# dRGBblades.net
KiCad netlist of a schematic drawn in EAGLE
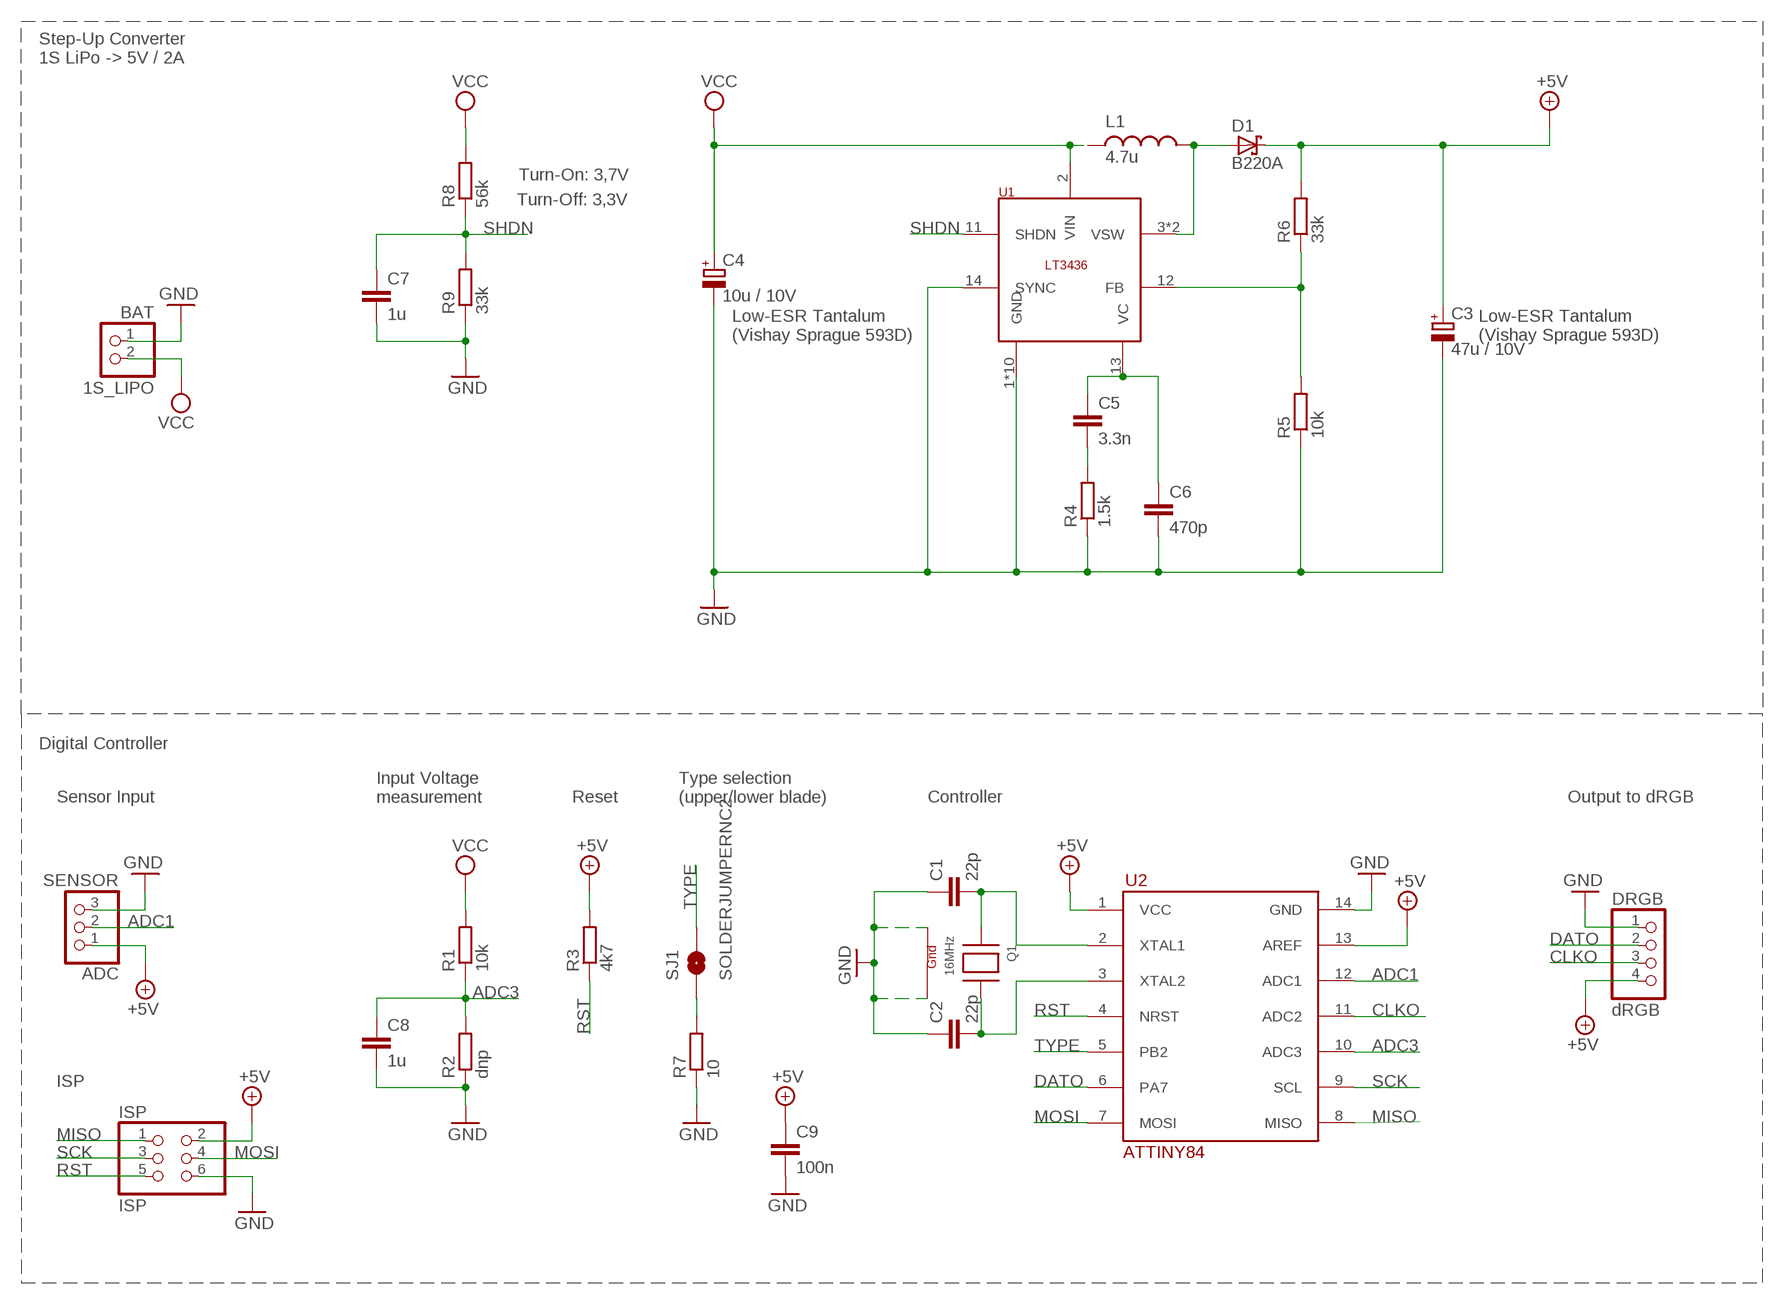
[diagram p0: schematic, sheet 1]

(export (version "E")
  (design (tool "Eeschema 10.0.6"))
  (components
    (comp (ref "ADC")
      (value "SENSOR")
      (footprint "eagle-import:1X03_90")
      (libsource (lib "eagle-import") (part "PINHD-1X3/90"))
    )
    (comp (ref "BAT")
      (value "1S_LIPO")
      (footprint "eagle-import:1X02_90")
      (libsource (lib "eagle-import") (part "PINHD-1X2/90"))
    )
    (comp (ref "C1")
      (value "22p")
      (footprint "eagle-import:C0603")
      (libsource (lib "eagle-import") (part "C-EUC0603"))
    )
    (comp (ref "C2")
      (value "22p")
      (footprint "eagle-import:C0603")
      (libsource (lib "eagle-import") (part "C-EUC0603"))
    )
    (comp (ref "C3")
      (value "47u / 10V")
      (footprint "eagle-import:D_7343-31W")
      (libsource (lib "eagle-import") (part "CPOL-EUD/7343-31W"))
    )
    (comp (ref "C4")
      (value "10u / 10V")
      (footprint "eagle-import:A_3216-18W")
      (libsource (lib "eagle-import") (part "CPOL-EUA/3216-18W"))
    )
    (comp (ref "C5")
      (value "3.3n")
      (footprint "eagle-import:C0603")
      (libsource (lib "eagle-import") (part "C-EUC0603"))
    )
    (comp (ref "C6")
      (value "470p")
      (footprint "eagle-import:C0603")
      (libsource (lib "eagle-import") (part "C-EUC0603"))
    )
    (comp (ref "C7")
      (value "1u")
      (footprint "eagle-import:C0603")
      (libsource (lib "eagle-import") (part "C-EUC0603"))
    )
    (comp (ref "C8")
      (value "1u")
      (footprint "eagle-import:C0603")
      (libsource (lib "eagle-import") (part "C-EUC0603"))
    )
    (comp (ref "C9")
      (value "100n")
      (footprint "eagle-import:C0603")
      (libsource (lib "eagle-import") (part "C-EUC0603"))
    )
    (comp (ref "D1")
      (value "B220A")
      (footprint "eagle-import:SMA")
      (libsource (lib "eagle-import") (part "B220A"))
    )
    (comp (ref "DRGB")
      (value "dRGB")
      (footprint "eagle-import:1X04_90")
      (libsource (lib "eagle-import") (part "PINHD-1X4/90"))
    )
    (comp (ref "ISP")
      (value "ISP")
      (footprint "eagle-import:2X03_90")
      (libsource (lib "eagle-import") (part "PINHD-2X3/90"))
    )
    (comp (ref "L1")
      (value "4.7u")
      (footprint "eagle-import:INDUCTOR-SUMIDA-CDRH6")
      (libsource (lib "eagle-import") (part "INDUCTOR-SUMIDA-CDRH6"))
    )
    (comp (ref "Q1")
      (value "16MHz")
      (footprint "eagle-import:NX3225")
      (libsource (lib "eagle-import") (part "XTAL-4-3225"))
    )
    (comp (ref "R1")
      (value "10k")
      (footprint "eagle-import:R0603")
      (libsource (lib "eagle-import") (part "R-EUR0603"))
    )
    (comp (ref "R2")
      (value "dnp")
      (footprint "eagle-import:R0603")
      (libsource (lib "eagle-import") (part "R-EUR0603"))
    )
    (comp (ref "R3")
      (value "4k7")
      (footprint "eagle-import:R0603")
      (libsource (lib "eagle-import") (part "R-EUR0603"))
    )
    (comp (ref "R4")
      (value "1.5k")
      (footprint "eagle-import:R0603")
      (libsource (lib "eagle-import") (part "R-EUR0603"))
    )
    (comp (ref "R5")
      (value "10k")
      (footprint "eagle-import:R0603")
      (libsource (lib "eagle-import") (part "R-EUR0603"))
    )
    (comp (ref "R6")
      (value "33k")
      (footprint "eagle-import:R0603")
      (libsource (lib "eagle-import") (part "R-EUR0603"))
    )
    (comp (ref "R7")
      (value "10")
      (footprint "eagle-import:R0603")
      (libsource (lib "eagle-import") (part "R-EUR0603"))
    )
    (comp (ref "R8")
      (value "56k")
      (footprint "eagle-import:R0603")
      (libsource (lib "eagle-import") (part "R-EUR0603"))
    )
    (comp (ref "R9")
      (value "33k")
      (footprint "eagle-import:R0603")
      (libsource (lib "eagle-import") (part "R-EUR0603"))
    )
    (comp (ref "SJ1")
      (value "SOLDERJUMPERNC2")
      (footprint "eagle-import:SJ_2S-NOTRACE")
      (libsource (lib "eagle-import") (part "SOLDERJUMPERNC2"))
    )
    (comp (ref "U1")
      (value "LT3436")
      (footprint "eagle-import:TSSOP-17")
      (libsource (lib "eagle-import") (part "LT3436"))
    )
    (comp (ref "U2")
      (value "ATTINY84")
      (footprint "eagle-import:SO14")
      (libsource (lib "eagle-import") (part "ATTINY84"))
    )
  )
  (nets
    (net (code "1") (name "+5V") (class "Default")
      (node (ref "ADC") (pin "1") (pinfunction "1_1") (pintype "passive"))
      (node (ref "C3") (pin "+") (pinfunction "+_+") (pintype "passive"))
      (node (ref "C9") (pin "1") (pinfunction "1_1") (pintype "passive"))
      (node (ref "D1") (pin "C") (pinfunction "C_C") (pintype "passive"))
      (node (ref "DRGB") (pin "4") (pinfunction "4_4") (pintype "passive"))
      (node (ref "ISP") (pin "2") (pinfunction "2_2") (pintype "passive"))
      (node (ref "R3") (pin "2") (pinfunction "2_2") (pintype "passive"))
      (node (ref "R6") (pin "2") (pinfunction "2_2") (pintype "passive"))
      (node (ref "U2") (pin "1") (pinfunction "VCC_1") (pintype "input"))
      (node (ref "U2") (pin "13") (pinfunction "AREF_13") (pintype "input"))
    )
    (net (code "2") (name "/ADC1") (class "Default")
      (node (ref "ADC") (pin "2") (pinfunction "2_2") (pintype "passive"))
      (node (ref "U2") (pin "12") (pinfunction "ADC1_12") (pintype "input"))
    )
    (net (code "3") (name "/ADC3") (class "Default")
      (node (ref "C8") (pin "1") (pinfunction "1_1") (pintype "passive"))
      (node (ref "R1") (pin "1") (pinfunction "1_1") (pintype "passive"))
      (node (ref "R2") (pin "2") (pinfunction "2_2") (pintype "passive"))
      (node (ref "U2") (pin "10") (pinfunction "ADC3_10") (pintype "input"))
    )
    (net (code "4") (name "/CLKO") (class "Default")
      (node (ref "DRGB") (pin "3") (pinfunction "3_3") (pintype "passive"))
      (node (ref "U2") (pin "11") (pinfunction "ADC2_11") (pintype "passive"))
    )
    (net (code "5") (name "/DATO") (class "Default")
      (node (ref "DRGB") (pin "2") (pinfunction "2_2") (pintype "passive"))
      (node (ref "U2") (pin "6") (pinfunction "PA7_6") (pintype "bidirectional"))
    )
    (net (code "6") (name "/MISO") (class "Default")
      (node (ref "ISP") (pin "1") (pinfunction "1_1") (pintype "passive"))
      (node (ref "U2") (pin "8") (pinfunction "MISO_8") (pintype "input"))
    )
    (net (code "7") (name "/MOSI") (class "Default")
      (node (ref "ISP") (pin "4") (pinfunction "4_4") (pintype "passive"))
      (node (ref "U2") (pin "7") (pinfunction "MOSI_7") (pintype "output"))
    )
    (net (code "8") (name "/RST") (class "Default")
      (node (ref "ISP") (pin "5") (pinfunction "5_5") (pintype "passive"))
      (node (ref "R3") (pin "1") (pinfunction "1_1") (pintype "passive"))
      (node (ref "U2") (pin "4") (pinfunction "NRST_4") (pintype "input"))
    )
    (net (code "9") (name "/SCK") (class "Default")
      (node (ref "ISP") (pin "3") (pinfunction "3_3") (pintype "passive"))
      (node (ref "U2") (pin "9") (pinfunction "SCL_9") (pintype "output"))
    )
    (net (code "10") (name "/SHDN") (class "Default")
      (node (ref "C7") (pin "1") (pinfunction "1_1") (pintype "passive"))
      (node (ref "R8") (pin "1") (pinfunction "1_1") (pintype "passive"))
      (node (ref "R9") (pin "2") (pinfunction "2_2") (pintype "passive"))
      (node (ref "U1") (pin "11") (pinfunction "SHDN_11") (pintype "input"))
    )
    (net (code "11") (name "/TYPE") (class "Default")
      (node (ref "SJ1") (pin "2") (pinfunction "2_2") (pintype "passive"))
      (node (ref "U2") (pin "5") (pinfunction "PB2_5") (pintype "bidirectional"))
    )
    (net (code "12") (name "GND") (class "Default")
      (node (ref "ADC") (pin "3") (pinfunction "3_3") (pintype "passive"))
      (node (ref "BAT") (pin "1") (pinfunction "1_1") (pintype "passive"))
      (node (ref "C1") (pin "1") (pinfunction "1_1") (pintype "passive"))
      (node (ref "C2") (pin "1") (pinfunction "1_1") (pintype "passive"))
      (node (ref "C3") (pin "-") (pinfunction "-_-") (pintype "passive"))
      (node (ref "C4") (pin "-") (pinfunction "-_-") (pintype "passive"))
      (node (ref "C6") (pin "2") (pinfunction "2_2") (pintype "passive"))
      (node (ref "C7") (pin "2") (pinfunction "2_2") (pintype "passive"))
      (node (ref "C8") (pin "2") (pinfunction "2_2") (pintype "passive"))
      (node (ref "C9") (pin "2") (pinfunction "2_2") (pintype "passive"))
      (node (ref "DRGB") (pin "1") (pinfunction "1_1") (pintype "passive"))
      (node (ref "ISP") (pin "6") (pinfunction "6_6") (pintype "passive"))
      (node (ref "Q1") (pin "2") (pinfunction "G2_2") (pintype "power_in"))
      (node (ref "Q1") (pin "4") (pinfunction "G1_4") (pintype "power_in"))
      (node (ref "R2") (pin "1") (pinfunction "1_1") (pintype "passive"))
      (node (ref "R4") (pin "1") (pinfunction "1_1") (pintype "passive"))
      (node (ref "R5") (pin "1") (pinfunction "1_1") (pintype "passive"))
      (node (ref "R7") (pin "1") (pinfunction "1_1") (pintype "passive"))
      (node (ref "R9") (pin "1") (pinfunction "1_1") (pintype "passive"))
      (node (ref "U1") (pin "1") (pinfunction "GND_1") (pintype "power_in"))
      (node (ref "U1") (pin "10") (pinfunction "GND_10") (pintype "power_in"))
      (node (ref "U1") (pin "14") (pinfunction "SYNC_14") (pintype "input"))
      (node (ref "U1") (pin "15") (pinfunction "GND_15") (pintype "power_in"))
      (node (ref "U1") (pin "16") (pinfunction "GND_16") (pintype "power_in"))
      (node (ref "U1") (pin "17") (pinfunction "GND_17") (pintype "power_in"))
      (node (ref "U1") (pin "5") (pinfunction "GND_5") (pintype "power_in"))
      (node (ref "U1") (pin "6") (pinfunction "GND_6") (pintype "power_in"))
      (node (ref "U1") (pin "7") (pinfunction "GND_7") (pintype "power_in"))
      (node (ref "U1") (pin "8") (pinfunction "GND_8") (pintype "power_in"))
      (node (ref "U1") (pin "9") (pinfunction "GND_9") (pintype "power_in"))
      (node (ref "U2") (pin "14") (pinfunction "GND_14") (pintype "power_in"))
    )
    (net (code "13") (name "Net-(C5-Pad2)") (class "Default")
      (node (ref "C5") (pin "2") (pinfunction "2_2") (pintype "passive"))
      (node (ref "R4") (pin "2") (pinfunction "2_2") (pintype "passive"))
    )
    (net (code "14") (name "Net-(D1-PadA)") (class "Default")
      (node (ref "D1") (pin "A") (pinfunction "A_A") (pintype "passive"))
      (node (ref "L1") (pin "P$2") (pinfunction "P$2_P$2") (pintype "bidirectional"))
      (node (ref "U1") (pin "3") (pinfunction "VSW_3") (pintype "output"))
      (node (ref "U1") (pin "4") (pinfunction "VSW_4") (pintype "output"))
    )
    (net (code "15") (name "Net-(Q1-X1)") (class "Default")
      (node (ref "C1") (pin "2") (pinfunction "2_2") (pintype "passive"))
      (node (ref "Q1") (pin "1") (pinfunction "X1_1") (pintype "bidirectional"))
      (node (ref "U2") (pin "2") (pinfunction "XTAL1_2") (pintype "bidirectional"))
    )
    (net (code "16") (name "Net-(Q1-X2)") (class "Default")
      (node (ref "C2") (pin "2") (pinfunction "2_2") (pintype "passive"))
      (node (ref "Q1") (pin "3") (pinfunction "X2_3") (pintype "bidirectional"))
      (node (ref "U2") (pin "3") (pinfunction "XTAL2_3") (pintype "bidirectional"))
    )
    (net (code "17") (name "Net-(R7-Pad2)") (class "Default")
      (node (ref "R7") (pin "2") (pinfunction "2_2") (pintype "passive"))
      (node (ref "SJ1") (pin "1") (pinfunction "1_1") (pintype "passive"))
    )
    (net (code "18") (name "Net-(U1-FB)") (class "Default")
      (node (ref "R5") (pin "2") (pinfunction "2_2") (pintype "passive"))
      (node (ref "R6") (pin "1") (pinfunction "1_1") (pintype "passive"))
      (node (ref "U1") (pin "12") (pinfunction "FB_12") (pintype "input"))
    )
    (net (code "19") (name "Net-(U1-VC)") (class "Default")
      (node (ref "C5") (pin "1") (pinfunction "1_1") (pintype "passive"))
      (node (ref "C6") (pin "1") (pinfunction "1_1") (pintype "passive"))
      (node (ref "U1") (pin "13") (pinfunction "VC_13") (pintype "output"))
    )
    (net (code "20") (name "VCC") (class "Default")
      (node (ref "BAT") (pin "2") (pinfunction "2_2") (pintype "passive"))
      (node (ref "C4") (pin "+") (pinfunction "+_+") (pintype "passive"))
      (node (ref "L1") (pin "P$1") (pinfunction "P$1_P$1") (pintype "bidirectional"))
      (node (ref "R1") (pin "2") (pinfunction "2_2") (pintype "passive"))
      (node (ref "R8") (pin "2") (pinfunction "2_2") (pintype "passive"))
      (node (ref "U1") (pin "2") (pinfunction "VIN_2") (pintype "input"))
    )
  )
)
